# LionDrillCharger.net
KiCad netlist of a schematic drawn in EAGLE
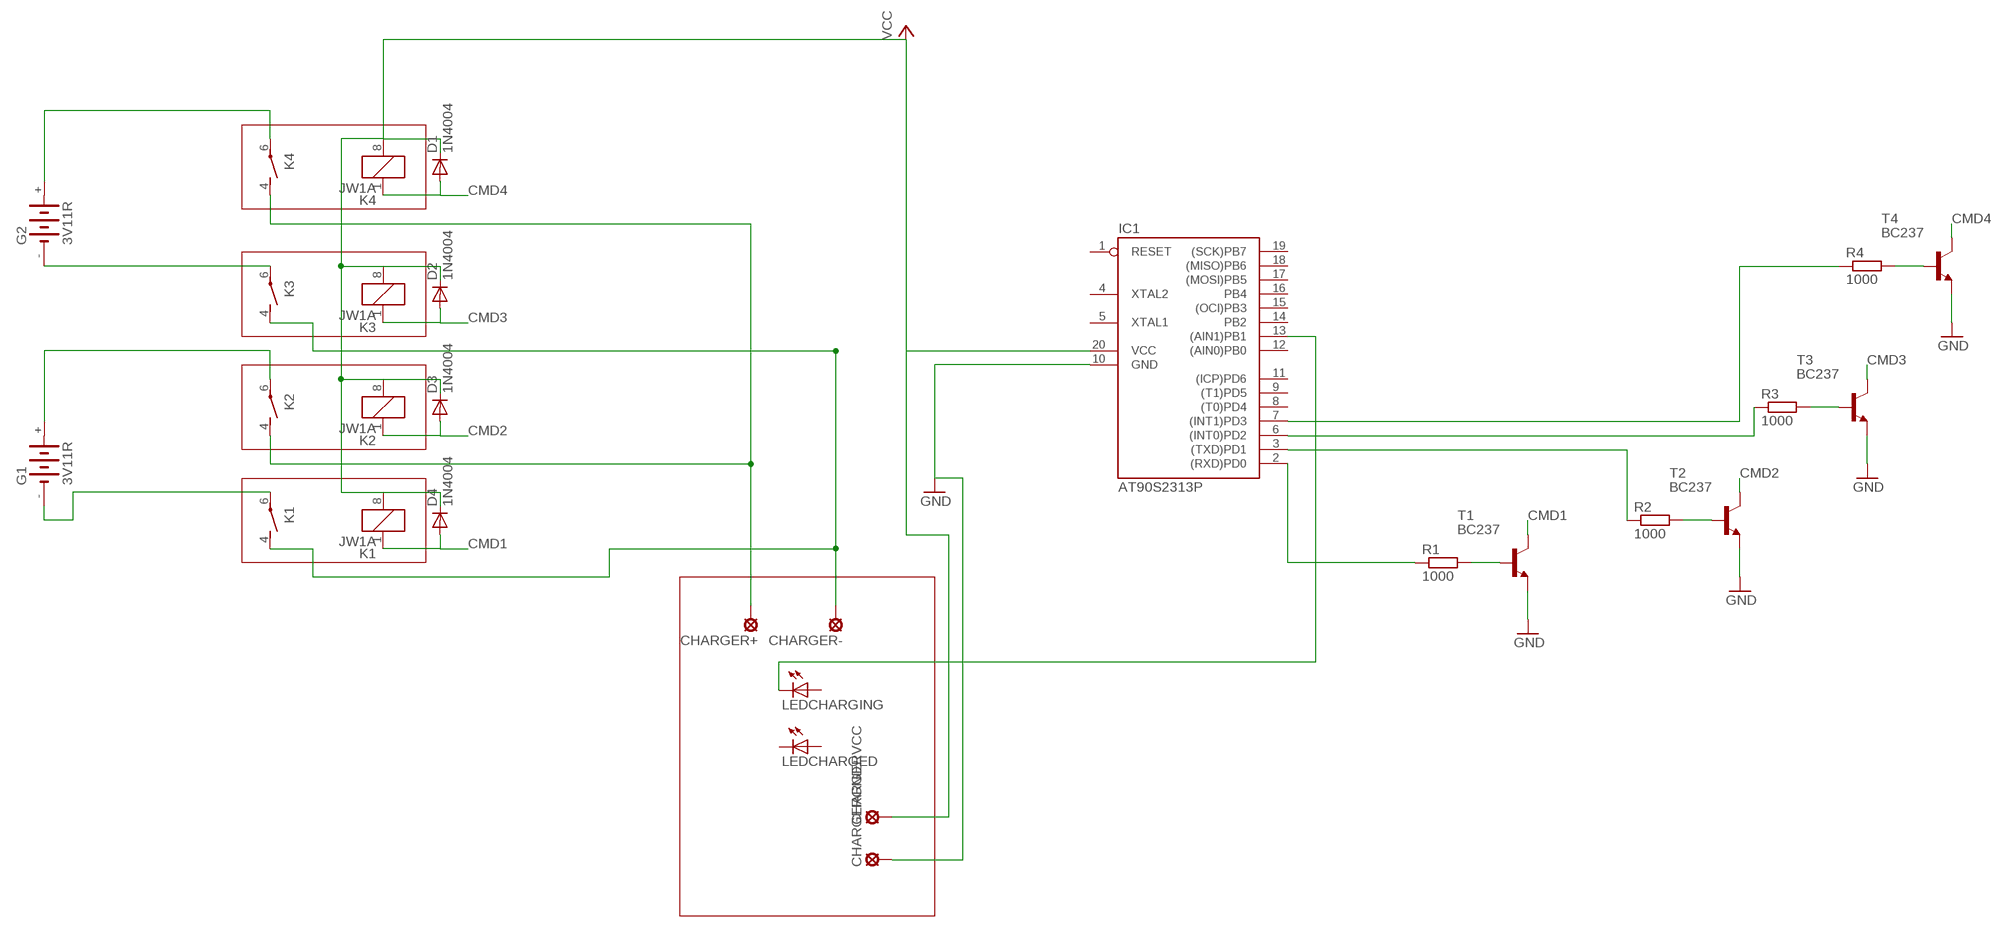
[diagram p0: schematic, sheet 1]

(export (version "E")
  (design (tool "Eeschema 10.0.6"))
  (components
    (comp (ref "CHARGER+")
      (value "LSP11")
      (footprint "eagle-import:LSP11")
      (libsource (lib "eagle-import") (part "LSP11"))
    )
    (comp (ref "CHARGER-")
      (value "LSP11")
      (footprint "eagle-import:LSP11")
      (libsource (lib "eagle-import") (part "LSP11"))
    )
    (comp (ref "CHARGERGND")
      (value "LSP11")
      (footprint "eagle-import:LSP11")
      (libsource (lib "eagle-import") (part "LSP11"))
    )
    (comp (ref "CHARGERVCC")
      (value "LSP11")
      (footprint "eagle-import:LSP11")
      (libsource (lib "eagle-import") (part "LSP11"))
    )
    (comp (ref "D1")
      (value "1N4004")
      (footprint "eagle-import:DO41-10")
      (libsource (lib "eagle-import") (part "1N4004"))
    )
    (comp (ref "D2")
      (value "1N4004")
      (footprint "eagle-import:DO41-10")
      (libsource (lib "eagle-import") (part "1N4004"))
    )
    (comp (ref "D3")
      (value "1N4004")
      (footprint "eagle-import:DO41-10")
      (libsource (lib "eagle-import") (part "1N4004"))
    )
    (comp (ref "D4")
      (value "1N4004")
      (footprint "eagle-import:DO41-10")
      (libsource (lib "eagle-import") (part "1N4004"))
    )
    (comp (ref "G1")
      (value "3V11R")
      (footprint "eagle-import:3V11R")
      (libsource (lib "eagle-import") (part "3V11R"))
    )
    (comp (ref "G2")
      (value "3V11R")
      (footprint "eagle-import:3V11R")
      (libsource (lib "eagle-import") (part "3V11R"))
    )
    (comp (ref "IC1")
      (value "AT90S2313P")
      (footprint "eagle-import:DIL20")
      (libsource (lib "eagle-import") (part "AT90S2313P"))
    )
    (comp (ref "K1")
      (value "JW1A")
      (footprint "eagle-import:JW1A")
      (libsource (lib "eagle-import") (part "JW1A"))
    )
    (comp (ref "K2")
      (value "JW1A")
      (footprint "eagle-import:JW1A")
      (libsource (lib "eagle-import") (part "JW1A"))
    )
    (comp (ref "K3")
      (value "JW1A")
      (footprint "eagle-import:JW1A")
      (libsource (lib "eagle-import") (part "JW1A"))
    )
    (comp (ref "K4")
      (value "JW1A")
      (footprint "eagle-import:JW1A")
      (libsource (lib "eagle-import") (part "JW1A"))
    )
    (comp (ref "LEDCHARGED")
      (value "LED3MM")
      (footprint "eagle-import:LED3MM")
      (libsource (lib "eagle-import") (part "LED3MM"))
    )
    (comp (ref "LEDCHARGING")
      (value "LED3MM")
      (footprint "eagle-import:LED3MM")
      (libsource (lib "eagle-import") (part "LED3MM"))
    )
    (comp (ref "R1")
      (value "1000")
      (footprint "eagle-import:0204_5")
      (libsource (lib "eagle-import") (part "R-EU_0204/5"))
    )
    (comp (ref "R2")
      (value "1000")
      (footprint "eagle-import:0204_5")
      (libsource (lib "eagle-import") (part "R-EU_0204/5"))
    )
    (comp (ref "R3")
      (value "1000")
      (footprint "eagle-import:0204_5")
      (libsource (lib "eagle-import") (part "R-EU_0204/5"))
    )
    (comp (ref "R4")
      (value "1000")
      (footprint "eagle-import:0204_5")
      (libsource (lib "eagle-import") (part "R-EU_0204/5"))
    )
    (comp (ref "T1")
      (value "BC237")
      (footprint "eagle-import:TO92")
      (libsource (lib "eagle-import") (part "BC237"))
    )
    (comp (ref "T2")
      (value "BC237")
      (footprint "eagle-import:TO92")
      (libsource (lib "eagle-import") (part "BC237"))
    )
    (comp (ref "T3")
      (value "BC237")
      (footprint "eagle-import:TO92")
      (libsource (lib "eagle-import") (part "BC237"))
    )
    (comp (ref "T4")
      (value "BC237")
      (footprint "eagle-import:TO92")
      (libsource (lib "eagle-import") (part "BC237"))
    )
  )
  (nets
    (net (code "1") (name "/CMD1") (class "Default")
      (node (ref "D4") (pin "A") (pinfunction "A_A") (pintype "passive"))
      (node (ref "K1") (pin "1") (pinfunction "1_1") (pintype "passive"))
      (node (ref "T1") (pin "3") (pinfunction "C_3") (pintype "passive"))
    )
    (net (code "2") (name "/CMD2") (class "Default")
      (node (ref "D3") (pin "A") (pinfunction "A_A") (pintype "passive"))
      (node (ref "K2") (pin "1") (pinfunction "1_1") (pintype "passive"))
      (node (ref "T2") (pin "3") (pinfunction "C_3") (pintype "passive"))
    )
    (net (code "3") (name "/CMD3") (class "Default")
      (node (ref "D2") (pin "A") (pinfunction "A_A") (pintype "passive"))
      (node (ref "K3") (pin "1") (pinfunction "1_1") (pintype "passive"))
      (node (ref "T3") (pin "3") (pinfunction "C_3") (pintype "passive"))
    )
    (net (code "4") (name "/CMD4") (class "Default")
      (node (ref "D1") (pin "A") (pinfunction "A_A") (pintype "passive"))
      (node (ref "K4") (pin "1") (pinfunction "1_1") (pintype "passive"))
      (node (ref "T4") (pin "3") (pinfunction "C_3") (pintype "passive"))
    )
    (net (code "5") (name "GND") (class "Default")
      (node (ref "CHARGERGND") (pin "MP") (pinfunction "MP_MP") (pintype "passive"))
      (node (ref "IC1") (pin "10") (pinfunction "GND_10") (pintype "power_in"))
      (node (ref "T1") (pin "1") (pinfunction "E_1") (pintype "passive"))
      (node (ref "T2") (pin "1") (pinfunction "E_1") (pintype "passive"))
      (node (ref "T3") (pin "1") (pinfunction "E_1") (pintype "passive"))
      (node (ref "T4") (pin "1") (pinfunction "E_1") (pintype "passive"))
    )
    (net (code "6") (name "Net-(IC1-(AIN1)PB1)") (class "Default")
      (node (ref "IC1") (pin "13") (pinfunction "(AIN1)PB1_13") (pintype "bidirectional"))
      (node (ref "LEDCHARGING") (pin "K") (pinfunction "C_K") (pintype "passive"))
    )
    (net (code "7") (name "Net-(IC1-(INT0)PD2)") (class "Default")
      (node (ref "IC1") (pin "6") (pinfunction "(INT0)PD2_6") (pintype "bidirectional"))
      (node (ref "R3") (pin "1") (pinfunction "1_1") (pintype "passive"))
    )
    (net (code "8") (name "Net-(IC1-(INT1)PD3)") (class "Default")
      (node (ref "IC1") (pin "7") (pinfunction "(INT1)PD3_7") (pintype "bidirectional"))
      (node (ref "R4") (pin "1") (pinfunction "1_1") (pintype "passive"))
    )
    (net (code "9") (name "Net-(IC1-(RXD)PD0)") (class "Default")
      (node (ref "IC1") (pin "2") (pinfunction "(RXD)PD0_2") (pintype "bidirectional"))
      (node (ref "R1") (pin "1") (pinfunction "1_1") (pintype "passive"))
    )
    (net (code "10") (name "Net-(IC1-(TXD)PD1)") (class "Default")
      (node (ref "IC1") (pin "3") (pinfunction "(TXD)PD1_3") (pintype "bidirectional"))
      (node (ref "R2") (pin "1") (pinfunction "1_1") (pintype "passive"))
    )
    (net (code "11") (name "Net-(K1A-P)") (class "Default")
      (node (ref "G1") (pin "-") (pinfunction "-_-") (pintype "passive"))
      (node (ref "K1") (pin "6") (pinfunction "P_6") (pintype "passive"))
    )
    (net (code "12") (name "Net-(K1A-S)") (class "Default")
      (node (ref "CHARGER-") (pin "MP") (pinfunction "MP_MP") (pintype "passive"))
      (node (ref "K1") (pin "4") (pinfunction "S_4") (pintype "passive"))
      (node (ref "K3") (pin "4") (pinfunction "S_4") (pintype "passive"))
    )
    (net (code "13") (name "Net-(K2A-P)") (class "Default")
      (node (ref "G1") (pin "+") (pinfunction "+_+") (pintype "passive"))
      (node (ref "K2") (pin "6") (pinfunction "P_6") (pintype "passive"))
    )
    (net (code "14") (name "Net-(K2A-S)") (class "Default")
      (node (ref "CHARGER+") (pin "MP") (pinfunction "MP_MP") (pintype "passive"))
      (node (ref "K2") (pin "4") (pinfunction "S_4") (pintype "passive"))
      (node (ref "K4") (pin "4") (pinfunction "S_4") (pintype "passive"))
    )
    (net (code "15") (name "Net-(K3A-P)") (class "Default")
      (node (ref "G2") (pin "-") (pinfunction "-_-") (pintype "passive"))
      (node (ref "K3") (pin "6") (pinfunction "P_6") (pintype "passive"))
    )
    (net (code "16") (name "Net-(K4A-P)") (class "Default")
      (node (ref "G2") (pin "+") (pinfunction "+_+") (pintype "passive"))
      (node (ref "K4") (pin "6") (pinfunction "P_6") (pintype "passive"))
    )
    (net (code "17") (name "Net-(T1-B)") (class "Default")
      (node (ref "R1") (pin "2") (pinfunction "2_2") (pintype "passive"))
      (node (ref "T1") (pin "2") (pinfunction "B_2") (pintype "passive"))
    )
    (net (code "18") (name "Net-(T2-B)") (class "Default")
      (node (ref "R2") (pin "2") (pinfunction "2_2") (pintype "passive"))
      (node (ref "T2") (pin "2") (pinfunction "B_2") (pintype "passive"))
    )
    (net (code "19") (name "Net-(T3-B)") (class "Default")
      (node (ref "R3") (pin "2") (pinfunction "2_2") (pintype "passive"))
      (node (ref "T3") (pin "2") (pinfunction "B_2") (pintype "passive"))
    )
    (net (code "20") (name "Net-(T4-B)") (class "Default")
      (node (ref "R4") (pin "2") (pinfunction "2_2") (pintype "passive"))
      (node (ref "T4") (pin "2") (pinfunction "B_2") (pintype "passive"))
    )
    (net (code "21") (name "VCC") (class "Default")
      (node (ref "CHARGERVCC") (pin "MP") (pinfunction "MP_MP") (pintype "passive"))
      (node (ref "D1") (pin "C") (pinfunction "C_C") (pintype "passive"))
      (node (ref "D2") (pin "C") (pinfunction "C_C") (pintype "passive"))
      (node (ref "D3") (pin "C") (pinfunction "C_C") (pintype "passive"))
      (node (ref "D4") (pin "C") (pinfunction "C_C") (pintype "passive"))
      (node (ref "IC1") (pin "20") (pinfunction "VCC_20") (pintype "power_in"))
      (node (ref "K1") (pin "8") (pinfunction "2_8") (pintype "passive"))
      (node (ref "K2") (pin "8") (pinfunction "2_8") (pintype "passive"))
      (node (ref "K3") (pin "8") (pinfunction "2_8") (pintype "passive"))
      (node (ref "K4") (pin "8") (pinfunction "2_8") (pintype "passive"))
    )
    (net (code "22") (name "unconnected-(IC1-(AIN0)PB0-Pad12)") (class "Default")
      (node (ref "IC1") (pin "12") (pinfunction "(AIN0)PB0_12") (pintype "bidirectional"))
    )
    (net (code "23") (name "unconnected-(IC1-(ICP)PD6-Pad11)") (class "Default")
      (node (ref "IC1") (pin "11") (pinfunction "(ICP)PD6_11") (pintype "bidirectional"))
    )
    (net (code "24") (name "unconnected-(IC1-(MISO)PB6-Pad18)") (class "Default")
      (node (ref "IC1") (pin "18") (pinfunction "(MISO)PB6_18") (pintype "bidirectional"))
    )
    (net (code "25") (name "unconnected-(IC1-(MOSI)PB5-Pad17)") (class "Default")
      (node (ref "IC1") (pin "17") (pinfunction "(MOSI)PB5_17") (pintype "bidirectional"))
    )
    (net (code "26") (name "unconnected-(IC1-(OCI)PB3-Pad15)") (class "Default")
      (node (ref "IC1") (pin "15") (pinfunction "(OCI)PB3_15") (pintype "bidirectional"))
    )
    (net (code "27") (name "unconnected-(IC1-(SCK)PB7-Pad19)") (class "Default")
      (node (ref "IC1") (pin "19") (pinfunction "(SCK)PB7_19") (pintype "bidirectional"))
    )
    (net (code "28") (name "unconnected-(IC1-(T0)PD4-Pad8)") (class "Default")
      (node (ref "IC1") (pin "8") (pinfunction "(T0)PD4_8") (pintype "bidirectional"))
    )
    (net (code "29") (name "unconnected-(IC1-(T1)PD5-Pad9)") (class "Default")
      (node (ref "IC1") (pin "9") (pinfunction "(T1)PD5_9") (pintype "bidirectional"))
    )
    (net (code "30") (name "unconnected-(IC1-PB2-Pad14)") (class "Default")
      (node (ref "IC1") (pin "14") (pinfunction "PB2_14") (pintype "bidirectional"))
    )
    (net (code "31") (name "unconnected-(IC1-PB4-Pad16)") (class "Default")
      (node (ref "IC1") (pin "16") (pinfunction "PB4_16") (pintype "bidirectional"))
    )
    (net (code "32") (name "unconnected-(IC1-RESET-Pad1)") (class "Default")
      (node (ref "IC1") (pin "1") (pinfunction "RESET_1") (pintype "bidirectional"))
    )
    (net (code "33") (name "unconnected-(IC1-XTAL1-Pad5)") (class "Default")
      (node (ref "IC1") (pin "5") (pinfunction "XTAL1_5") (pintype "bidirectional"))
    )
    (net (code "34") (name "unconnected-(IC1-XTAL2-Pad4)") (class "Default")
      (node (ref "IC1") (pin "4") (pinfunction "XTAL2_4") (pintype "bidirectional"))
    )
    (net (code "35") (name "unconnected-(LEDCHARGED-C-PadK)") (class "Default")
      (node (ref "LEDCHARGED") (pin "K") (pinfunction "C_K") (pintype "passive"))
    )
    (net (code "36") (name "unconnected-(LEDCHARGED-PadA)") (class "Default")
      (node (ref "LEDCHARGED") (pin "A") (pinfunction "A_A") (pintype "passive"))
    )
    (net (code "37") (name "unconnected-(LEDCHARGING-PadA)") (class "Default")
      (node (ref "LEDCHARGING") (pin "A") (pinfunction "A_A") (pintype "passive"))
    )
  )
)
